# clock_circ.net
KiCad netlist of a schematic drawn in EAGLE
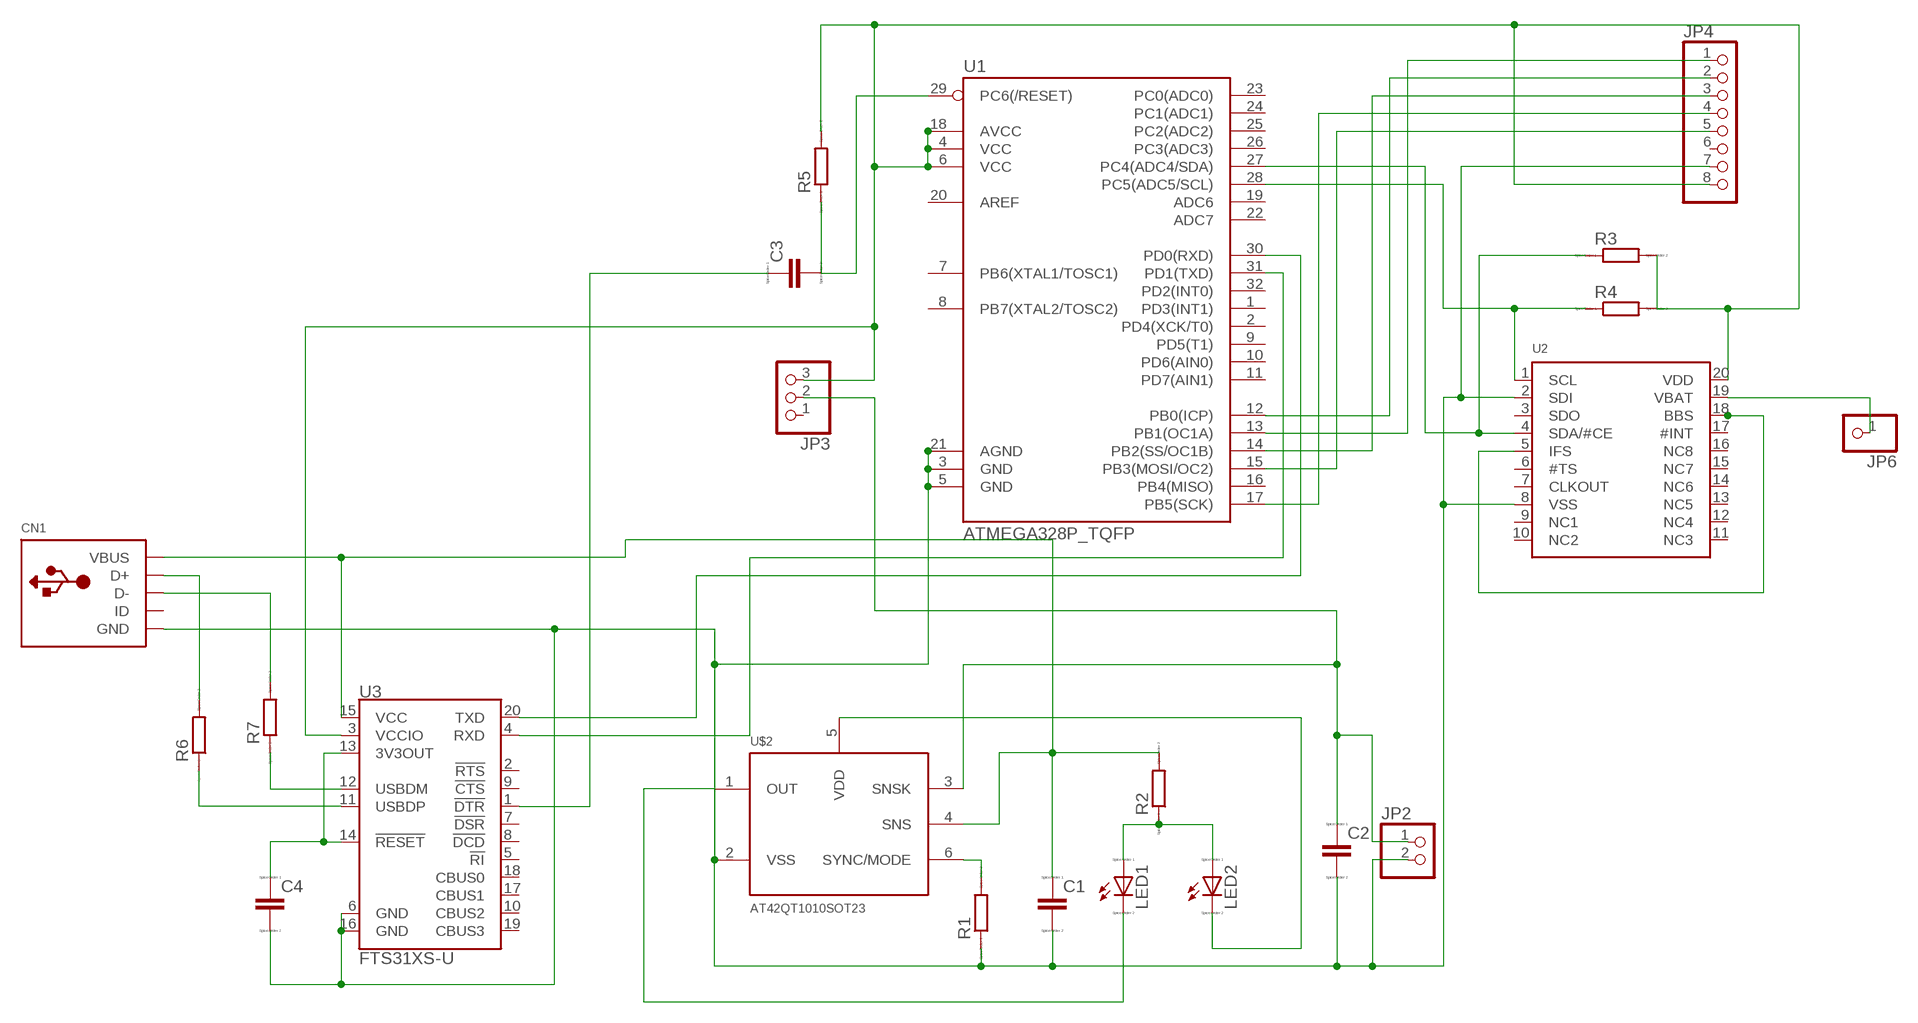
[diagram p0: schematic, sheet 1]

(export (version "E")
  (design (tool "Eeschema 10.0.6"))
  (components
    (comp (ref "C1")
      (value "CC1005")
      (footprint "eagle-import:C1005")
      (libsource (lib "eagle-import") (part "CC1005"))
    )
    (comp (ref "C2")
      (value "CC1005")
      (footprint "eagle-import:C1005")
      (libsource (lib "eagle-import") (part "CC1005"))
    )
    (comp (ref "C3")
      (value "CC0603")
      (footprint "eagle-import:C0603")
      (libsource (lib "eagle-import") (part "CC0603"))
    )
    (comp (ref "C4")
      (value "CC1005")
      (footprint "eagle-import:C1005")
      (libsource (lib "eagle-import") (part "CC1005"))
    )
    (comp (ref "CN1")
      (value "USBMINIB")
      (footprint "eagle-import:USB-MINIB")
      (libsource (lib "eagle-import") (part "USBMINIB"))
    )
    (comp (ref "JP2")
      (value "PINHD-1X2")
      (footprint "eagle-import:1X02")
      (libsource (lib "eagle-import") (part "PINHD-1X2"))
    )
    (comp (ref "JP3")
      (value "PINHD-1X3")
      (footprint "eagle-import:1X03")
      (libsource (lib "eagle-import") (part "PINHD-1X3"))
    )
    (comp (ref "JP4")
      (value "HEADER-1X8")
      (footprint "eagle-import:1X08_OVAL")
      (libsource (lib "eagle-import") (part "HEADER-1X8"))
    )
    (comp (ref "JP6")
      (value "PINHD-1X1")
      (footprint "eagle-import:1X01")
      (libsource (lib "eagle-import") (part "PINHD-1X1"))
    )
    (comp (ref "LED1")
      (value "LED_E")
      (footprint "eagle-import:LED_1206")
      (libsource (lib "eagle-import") (part "LED_E"))
    )
    (comp (ref "LED2")
      (value "LED_E")
      (footprint "eagle-import:LED_1206")
      (libsource (lib "eagle-import") (part "LED_E"))
    )
    (comp (ref "R1")
      (value "RR0603")
      (footprint "eagle-import:R0603")
      (libsource (lib "eagle-import") (part "RR0603"))
    )
    (comp (ref "R2")
      (value "RR0603")
      (footprint "eagle-import:R0603")
      (libsource (lib "eagle-import") (part "RR0603"))
    )
    (comp (ref "R3")
      (value "RR0603")
      (footprint "eagle-import:R0603")
      (libsource (lib "eagle-import") (part "RR0603"))
    )
    (comp (ref "R4")
      (value "RR0603")
      (footprint "eagle-import:R0603")
      (libsource (lib "eagle-import") (part "RR0603"))
    )
    (comp (ref "R5")
      (value "RR0603")
      (footprint "eagle-import:R0603")
      (libsource (lib "eagle-import") (part "RR0603"))
    )
    (comp (ref "R6")
      (value "RR0603")
      (footprint "eagle-import:R0603")
      (libsource (lib "eagle-import") (part "RR0603"))
    )
    (comp (ref "R7")
      (value "RR0603")
      (footprint "eagle-import:R0603")
      (libsource (lib "eagle-import") (part "RR0603"))
    )
    (comp (ref "U$2")
      (value "AT42QT1010SOT23")
      (footprint "eagle-import:SOT23-6")
      (libsource (lib "eagle-import") (part "AT42QT1010SOT23"))
    )
    (comp (ref "U1")
      (value "ATMEGA328P_TQFP")
      (footprint "eagle-import:TQFP32-08")
      (libsource (lib "eagle-import") (part "ATMEGA328P_TQFP"))
    )
    (comp (ref "U2")
      (value "RTC_PCF2129A")
      (footprint "eagle-import:SOIC20WIDE")
      (fields (field (name "PARTNO") "PCF2129AT/1,512"))
      (libsource (lib "eagle-import") (part "RTC_PCF2129A"))
    )
    (comp (ref "U3")
      (value "FTS31XS-U")
      (footprint "eagle-import:SSOP20_L")
      (libsource (lib "eagle-import") (part "FT231XS"))
    )
  )
  (nets
    (net (code "1") (name "Net-(CN1-PadD+)") (class "Default")
      (node (ref "CN1") (pin "D+") (pinfunction "D+_D+") (pintype "bidirectional"))
      (node (ref "R6") (pin "2") (pinfunction "2_2") (pintype "passive"))
    )
    (net (code "2") (name "Net-(CN1-PadD-)") (class "Default")
      (node (ref "CN1") (pin "D-") (pinfunction "D-_D-") (pintype "bidirectional"))
      (node (ref "R7") (pin "2") (pinfunction "2_2") (pintype "passive"))
    )
    (net (code "3") (name "Net-(LED1-PadA)") (class "Default")
      (node (ref "LED1") (pin "A") (pinfunction "A_A") (pintype "passive"))
      (node (ref "LED2") (pin "A") (pinfunction "A_A") (pintype "passive"))
      (node (ref "R2") (pin "1") (pinfunction "1_1") (pintype "passive"))
    )
    (net (code "4") (name "Net-(U$2-OUT)") (class "Default")
      (node (ref "LED1") (pin "C") (pinfunction "C_C") (pintype "passive"))
      (node (ref "U$2") (pin "1") (pinfunction "OUT_1") (pintype "bidirectional"))
    )
    (net (code "5") (name "Net-(U$2-SNS)") (class "Default")
      (node (ref "C1") (pin "1") (pinfunction "1_1") (pintype "passive"))
      (node (ref "CN1") (pin "VBUS") (pinfunction "VBUS_VBUS") (pintype "power_in"))
      (node (ref "R2") (pin "2") (pinfunction "2_2") (pintype "passive"))
      (node (ref "U$2") (pin "4") (pinfunction "SNS_4") (pintype "bidirectional"))
      (node (ref "U3") (pin "15") (pinfunction "VCC_15") (pintype "bidirectional"))
    )
    (net (code "6") (name "Net-(U$2-SNSK)") (class "Default")
      (node (ref "C2") (pin "1") (pinfunction "1_1") (pintype "passive"))
      (node (ref "JP2") (pin "1") (pinfunction "1_1") (pintype "passive"))
      (node (ref "JP3") (pin "2") (pinfunction "2_2") (pintype "passive"))
      (node (ref "U$2") (pin "3") (pinfunction "SNSK_3") (pintype "bidirectional"))
    )
    (net (code "7") (name "Net-(U$2-SYNC{slash}MODE)") (class "Default")
      (node (ref "R1") (pin "2") (pinfunction "2_2") (pintype "passive"))
      (node (ref "U$2") (pin "6") (pinfunction "SYNC/MODE_6") (pintype "bidirectional"))
    )
    (net (code "8") (name "Net-(U$2-VDD)") (class "Default")
      (node (ref "LED2") (pin "C") (pinfunction "C_C") (pintype "passive"))
      (node (ref "U$2") (pin "5") (pinfunction "VDD_5") (pintype "bidirectional"))
    )
    (net (code "9") (name "Net-(U$2-VSS)") (class "Default")
      (node (ref "C1") (pin "2") (pinfunction "2_2") (pintype "passive"))
      (node (ref "C2") (pin "2") (pinfunction "2_2") (pintype "passive"))
      (node (ref "C4") (pin "2") (pinfunction "2_2") (pintype "passive"))
      (node (ref "CN1") (pin "GND") (pinfunction "GND_GND") (pintype "power_in"))
      (node (ref "JP2") (pin "2") (pinfunction "2_2") (pintype "passive"))
      (node (ref "JP4") (pin "7") (pinfunction "7_7") (pintype "passive"))
      (node (ref "R1") (pin "1") (pinfunction "1_1") (pintype "passive"))
      (node (ref "U$2") (pin "2") (pinfunction "VSS_2") (pintype "bidirectional"))
      (node (ref "U1") (pin "21") (pinfunction "AGND_21") (pintype "bidirectional"))
      (node (ref "U1") (pin "3") (pinfunction "GND_3") (pintype "bidirectional"))
      (node (ref "U1") (pin "5") (pinfunction "GND_5") (pintype "bidirectional"))
      (node (ref "U2") (pin "2") (pinfunction "SDI_2") (pintype "bidirectional"))
      (node (ref "U2") (pin "8") (pinfunction "VSS_8") (pintype "bidirectional"))
      (node (ref "U3") (pin "16") (pinfunction "GND_16") (pintype "bidirectional"))
      (node (ref "U3") (pin "6") (pinfunction "GND_6") (pintype "bidirectional"))
    )
    (net (code "10") (name "Net-(U1-AVCC)") (class "Default")
      (node (ref "JP3") (pin "3") (pinfunction "3_3") (pintype "passive"))
      (node (ref "JP4") (pin "8") (pinfunction "8_8") (pintype "passive"))
      (node (ref "R3") (pin "2") (pinfunction "2_2") (pintype "passive"))
      (node (ref "R4") (pin "2") (pinfunction "2_2") (pintype "passive"))
      (node (ref "R5") (pin "2") (pinfunction "2_2") (pintype "passive"))
      (node (ref "U1") (pin "18") (pinfunction "AVCC_18") (pintype "bidirectional"))
      (node (ref "U1") (pin "4") (pinfunction "VCC_4") (pintype "bidirectional"))
      (node (ref "U1") (pin "6") (pinfunction "VCC_6") (pintype "bidirectional"))
      (node (ref "U2") (pin "20") (pinfunction "VDD_20") (pintype "bidirectional"))
      (node (ref "U3") (pin "3") (pinfunction "VCCIO_3") (pintype "bidirectional"))
    )
    (net (code "11") (name "Net-(U1-PB0(ICP))") (class "Default")
      (node (ref "JP4") (pin "2") (pinfunction "2_2") (pintype "passive"))
      (node (ref "U1") (pin "12") (pinfunction "PB0(ICP)_12") (pintype "bidirectional"))
    )
    (net (code "12") (name "Net-(U1-PB1(OC1A))") (class "Default")
      (node (ref "JP4") (pin "1") (pinfunction "1_1") (pintype "passive"))
      (node (ref "U1") (pin "13") (pinfunction "PB1(OC1A)_13") (pintype "bidirectional"))
    )
    (net (code "13") (name "Net-(U1-PB2(SS{slash}OC1B))") (class "Default")
      (node (ref "JP4") (pin "3") (pinfunction "3_3") (pintype "passive"))
      (node (ref "U1") (pin "14") (pinfunction "PB2(SS/OC1B)_14") (pintype "bidirectional"))
    )
    (net (code "14") (name "Net-(U1-PB3(MOSI{slash}OC2))") (class "Default")
      (node (ref "JP4") (pin "5") (pinfunction "5_5") (pintype "passive"))
      (node (ref "U1") (pin "15") (pinfunction "PB3(MOSI/OC2)_15") (pintype "bidirectional"))
    )
    (net (code "15") (name "Net-(U1-PB5(SCK))") (class "Default")
      (node (ref "JP4") (pin "4") (pinfunction "4_4") (pintype "passive"))
      (node (ref "U1") (pin "17") (pinfunction "PB5(SCK)_17") (pintype "bidirectional"))
    )
    (net (code "16") (name "Net-(U1-PC4(ADC4{slash}SDA))") (class "Default")
      (node (ref "R3") (pin "1") (pinfunction "1_1") (pintype "passive"))
      (node (ref "U1") (pin "27") (pinfunction "PC4(ADC4/SDA)_27") (pintype "bidirectional"))
      (node (ref "U2") (pin "4") (pinfunction "SDA/#CE_4") (pintype "bidirectional"))
    )
    (net (code "17") (name "Net-(U1-PC5(ADC5{slash}SCL))") (class "Default")
      (node (ref "R4") (pin "1") (pinfunction "1_1") (pintype "passive"))
      (node (ref "U1") (pin "28") (pinfunction "PC5(ADC5/SCL)_28") (pintype "bidirectional"))
      (node (ref "U2") (pin "1") (pinfunction "SCL_1") (pintype "bidirectional"))
    )
    (net (code "18") (name "Net-(U1-PC6({slash}RESET))") (class "Default")
      (node (ref "C3") (pin "2") (pinfunction "2_2") (pintype "passive"))
      (node (ref "R5") (pin "1") (pinfunction "1_1") (pintype "passive"))
      (node (ref "U1") (pin "29") (pinfunction "PC6(/RESET)_29") (pintype "bidirectional"))
    )
    (net (code "19") (name "Net-(U1-PD0(RXD))") (class "Default")
      (node (ref "U1") (pin "30") (pinfunction "PD0(RXD)_30") (pintype "bidirectional"))
      (node (ref "U3") (pin "20") (pinfunction "TXD_20") (pintype "bidirectional"))
    )
    (net (code "20") (name "Net-(U1-PD1(TXD))") (class "Default")
      (node (ref "U1") (pin "31") (pinfunction "PD1(TXD)_31") (pintype "bidirectional"))
      (node (ref "U3") (pin "4") (pinfunction "RXD_4") (pintype "bidirectional"))
    )
    (net (code "21") (name "Net-(U2-BBS)") (class "Default")
      (node (ref "U2") (pin "18") (pinfunction "BBS_18") (pintype "bidirectional"))
      (node (ref "U2") (pin "5") (pinfunction "IFS_5") (pintype "bidirectional"))
    )
    (net (code "22") (name "Net-(U2-VBAT)") (class "Default")
      (node (ref "JP6") (pin "1") (pinfunction "1_1") (pintype "passive"))
      (node (ref "U2") (pin "19") (pinfunction "VBAT_19") (pintype "bidirectional"))
    )
    (net (code "23") (name "Net-(U3-3V3OUT)") (class "Default")
      (node (ref "C4") (pin "1") (pinfunction "1_1") (pintype "passive"))
      (node (ref "U3") (pin "13") (pinfunction "3V3OUT_13") (pintype "bidirectional"))
      (node (ref "U3") (pin "14") (pinfunction "~{RESET}_14") (pintype "bidirectional"))
    )
    (net (code "24") (name "Net-(U3-USBDM)") (class "Default")
      (node (ref "R7") (pin "1") (pinfunction "1_1") (pintype "passive"))
      (node (ref "U3") (pin "12") (pinfunction "USBDM_12") (pintype "bidirectional"))
    )
    (net (code "25") (name "Net-(U3-USBDP)") (class "Default")
      (node (ref "R6") (pin "1") (pinfunction "1_1") (pintype "passive"))
      (node (ref "U3") (pin "11") (pinfunction "USBDP_11") (pintype "bidirectional"))
    )
    (net (code "26") (name "Net-(U3-~{DTR})") (class "Default")
      (node (ref "C3") (pin "1") (pinfunction "1_1") (pintype "passive"))
      (node (ref "U3") (pin "1") (pinfunction "~{DTR}_1") (pintype "bidirectional"))
    )
    (net (code "27") (name "unconnected-(CN1-PadID)") (class "Default")
      (node (ref "CN1") (pin "ID") (pinfunction "ID_ID") (pintype "bidirectional"))
    )
    (net (code "28") (name "unconnected-(JP3-Pad1)") (class "Default")
      (node (ref "JP3") (pin "1") (pinfunction "1_1") (pintype "passive"))
    )
    (net (code "29") (name "unconnected-(JP4-Pad6)") (class "Default")
      (node (ref "JP4") (pin "6") (pinfunction "6_6") (pintype "passive"))
    )
    (net (code "30") (name "unconnected-(U1-ADC6-Pad19)") (class "Default")
      (node (ref "U1") (pin "19") (pinfunction "ADC6_19") (pintype "bidirectional"))
    )
    (net (code "31") (name "unconnected-(U1-ADC7-Pad22)") (class "Default")
      (node (ref "U1") (pin "22") (pinfunction "ADC7_22") (pintype "bidirectional"))
    )
    (net (code "32") (name "unconnected-(U1-AREF-Pad20)") (class "Default")
      (node (ref "U1") (pin "20") (pinfunction "AREF_20") (pintype "bidirectional"))
    )
    (net (code "33") (name "unconnected-(U1-PB4(MISO)-Pad16)") (class "Default")
      (node (ref "U1") (pin "16") (pinfunction "PB4(MISO)_16") (pintype "bidirectional"))
    )
    (net (code "34") (name "unconnected-(U1-PB6(XTAL1{slash}TOSC1)-Pad7)") (class "Default")
      (node (ref "U1") (pin "7") (pinfunction "PB6(XTAL1/TOSC1)_7") (pintype "bidirectional"))
    )
    (net (code "35") (name "unconnected-(U1-PB7(XTAL2{slash}TOSC2)-Pad8)") (class "Default")
      (node (ref "U1") (pin "8") (pinfunction "PB7(XTAL2/TOSC2)_8") (pintype "bidirectional"))
    )
    (net (code "36") (name "unconnected-(U1-PC0(ADC0)-Pad23)") (class "Default")
      (node (ref "U1") (pin "23") (pinfunction "PC0(ADC0)_23") (pintype "bidirectional"))
    )
    (net (code "37") (name "unconnected-(U1-PC1(ADC1)-Pad24)") (class "Default")
      (node (ref "U1") (pin "24") (pinfunction "PC1(ADC1)_24") (pintype "bidirectional"))
    )
    (net (code "38") (name "unconnected-(U1-PC2(ADC2)-Pad25)") (class "Default")
      (node (ref "U1") (pin "25") (pinfunction "PC2(ADC2)_25") (pintype "bidirectional"))
    )
    (net (code "39") (name "unconnected-(U1-PC3(ADC3)-Pad26)") (class "Default")
      (node (ref "U1") (pin "26") (pinfunction "PC3(ADC3)_26") (pintype "bidirectional"))
    )
    (net (code "40") (name "unconnected-(U1-PD2(INT0)-Pad32)") (class "Default")
      (node (ref "U1") (pin "32") (pinfunction "PD2(INT0)_32") (pintype "bidirectional"))
    )
    (net (code "41") (name "unconnected-(U1-PD3(INT1)-Pad1)") (class "Default")
      (node (ref "U1") (pin "1") (pinfunction "PD3(INT1)_1") (pintype "bidirectional"))
    )
    (net (code "42") (name "unconnected-(U1-PD4(XCK{slash}T0)-Pad2)") (class "Default")
      (node (ref "U1") (pin "2") (pinfunction "PD4(XCK/T0)_2") (pintype "bidirectional"))
    )
    (net (code "43") (name "unconnected-(U1-PD5(T1)-Pad9)") (class "Default")
      (node (ref "U1") (pin "9") (pinfunction "PD5(T1)_9") (pintype "bidirectional"))
    )
    (net (code "44") (name "unconnected-(U1-PD6(AIN0)-Pad10)") (class "Default")
      (node (ref "U1") (pin "10") (pinfunction "PD6(AIN0)_10") (pintype "bidirectional"))
    )
    (net (code "45") (name "unconnected-(U1-PD7(AIN1)-Pad11)") (class "Default")
      (node (ref "U1") (pin "11") (pinfunction "PD7(AIN1)_11") (pintype "bidirectional"))
    )
    (net (code "46") (name "unconnected-(U2-#INT-Pad17)") (class "Default")
      (node (ref "U2") (pin "17") (pinfunction "#INT_17") (pintype "bidirectional"))
    )
    (net (code "47") (name "unconnected-(U2-#TS-Pad6)") (class "Default")
      (node (ref "U2") (pin "6") (pinfunction "#TS_6") (pintype "bidirectional"))
    )
    (net (code "48") (name "unconnected-(U2-CLKOUT-Pad7)") (class "Default")
      (node (ref "U2") (pin "7") (pinfunction "CLKOUT_7") (pintype "bidirectional"))
    )
    (net (code "49") (name "unconnected-(U2-NC1-Pad9)") (class "Default")
      (node (ref "U2") (pin "9") (pinfunction "NC1_9") (pintype "bidirectional"))
    )
    (net (code "50") (name "unconnected-(U2-NC2-Pad10)") (class "Default")
      (node (ref "U2") (pin "10") (pinfunction "NC2_10") (pintype "bidirectional"))
    )
    (net (code "51") (name "unconnected-(U2-NC3-Pad11)") (class "Default")
      (node (ref "U2") (pin "11") (pinfunction "NC3_11") (pintype "bidirectional"))
    )
    (net (code "52") (name "unconnected-(U2-NC4-Pad12)") (class "Default")
      (node (ref "U2") (pin "12") (pinfunction "NC4_12") (pintype "bidirectional"))
    )
    (net (code "53") (name "unconnected-(U2-NC5-Pad13)") (class "Default")
      (node (ref "U2") (pin "13") (pinfunction "NC5_13") (pintype "bidirectional"))
    )
    (net (code "54") (name "unconnected-(U2-NC6-Pad14)") (class "Default")
      (node (ref "U2") (pin "14") (pinfunction "NC6_14") (pintype "bidirectional"))
    )
    (net (code "55") (name "unconnected-(U2-NC7-Pad15)") (class "Default")
      (node (ref "U2") (pin "15") (pinfunction "NC7_15") (pintype "bidirectional"))
    )
    (net (code "56") (name "unconnected-(U2-NC8-Pad16)") (class "Default")
      (node (ref "U2") (pin "16") (pinfunction "NC8_16") (pintype "bidirectional"))
    )
    (net (code "57") (name "unconnected-(U2-SDO-Pad3)") (class "Default")
      (node (ref "U2") (pin "3") (pinfunction "SDO_3") (pintype "bidirectional"))
    )
    (net (code "58") (name "unconnected-(U3-CBUS0-Pad18)") (class "Default")
      (node (ref "U3") (pin "18") (pinfunction "CBUS0_18") (pintype "bidirectional"))
    )
    (net (code "59") (name "unconnected-(U3-CBUS1-Pad17)") (class "Default")
      (node (ref "U3") (pin "17") (pinfunction "CBUS1_17") (pintype "bidirectional"))
    )
    (net (code "60") (name "unconnected-(U3-CBUS2-Pad10)") (class "Default")
      (node (ref "U3") (pin "10") (pinfunction "CBUS2_10") (pintype "bidirectional"))
    )
    (net (code "61") (name "unconnected-(U3-CBUS3-Pad19)") (class "Default")
      (node (ref "U3") (pin "19") (pinfunction "CBUS3_19") (pintype "bidirectional"))
    )
    (net (code "62") (name "unconnected-(U3-~{CTS}-Pad9)") (class "Default")
      (node (ref "U3") (pin "9") (pinfunction "~{CTS}_9") (pintype "bidirectional"))
    )
    (net (code "63") (name "unconnected-(U3-~{DCD}-Pad8)") (class "Default")
      (node (ref "U3") (pin "8") (pinfunction "~{DCD}_8") (pintype "bidirectional"))
    )
    (net (code "64") (name "unconnected-(U3-~{DSR}-Pad7)") (class "Default")
      (node (ref "U3") (pin "7") (pinfunction "~{DSR}_7") (pintype "bidirectional"))
    )
    (net (code "65") (name "unconnected-(U3-~{RI}-Pad5)") (class "Default")
      (node (ref "U3") (pin "5") (pinfunction "~{RI}_5") (pintype "bidirectional"))
    )
    (net (code "66") (name "unconnected-(U3-~{RTS}-Pad2)") (class "Default")
      (node (ref "U3") (pin "2") (pinfunction "~{RTS}_2") (pintype "bidirectional"))
    )
  )
)
